# Schematic.net
KiCad netlist of a schematic drawn in Altium Designer
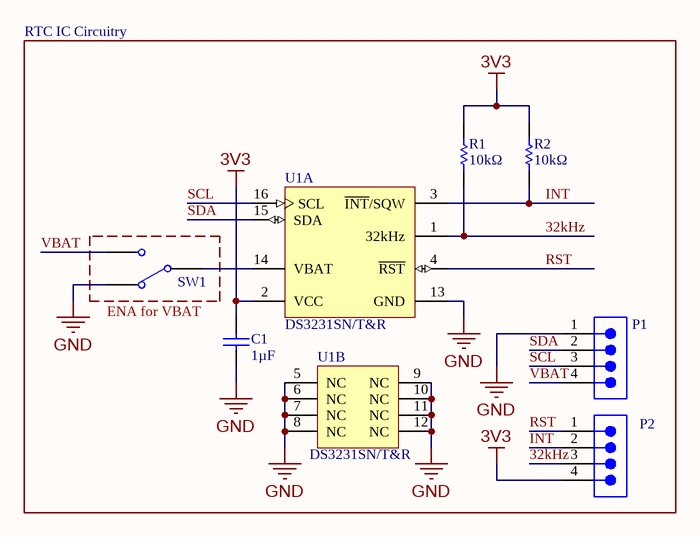
[diagram p0: Schematic.SchDoc]

(export (version "E")
  (design (tool "Eeschema 10.0.6"))
  (components
    (comp (ref "C1")
      (value "1µF")
      (footprint "CAPC3216X110X50LL20T25")
      (description "Chip Capacitor, 1 uF, +/- 10%, 50 V, -55 to 125 degC, 1206 (3216 Metric), RoHS, Tape and Reel")
      (fields (field (name "MANUFACTURER") "Kemet") (field (name "TOLERANCE") "10%"))
      (libsource (lib "Altium Content Vault") (part "CAP-NP-2"))
    )
    (comp (ref "P1")
      (value "61300411121")
      (footprint "61300411121")
      (libsource (lib "Altium Content Vault") (part "Header_Male_1R_04P"))
    )
    (comp (ref "P2")
      (value "61300411121")
      (footprint "61300411121")
      (libsource (lib "Altium Content Vault") (part "Header_Male_1R_04P"))
    )
    (comp (ref "R1")
      (value "10kΩ")
      (footprint "RESC3116X65X40LL10T20")
      (description "Chip Resistor, 10 KOhm, +/- 1%, 0.25 W, -55 to 155 degC, 1206 (3216 Metric), RoHS, Tape and Reel")
      (fields (field (name "TOLERANCE") "1%") (field (name "MANUFACTURER") "Yageo"))
      (libsource (lib "Altium Content Vault") (part "RES-2"))
    )
    (comp (ref "R2")
      (value "10kΩ")
      (footprint "RESC3116X65X40LL10T20")
      (description "Chip Resistor, 10 KOhm, +/- 1%, 0.25 W, -55 to 155 degC, 1206 (3216 Metric), RoHS, Tape and Reel")
      (fields (field (name "TOLERANCE") "1%") (field (name "MANUFACTURER") "Yageo"))
      (libsource (lib "Altium Content Vault") (part "RES-2"))
    )
    (comp (ref "SW1")
      (value "450404015514")
      (footprint "450404015514")
      (description "450404015514 Slide Switch, 0.3A, 5Vdc, Smd Rohs Compliant: Yes")
      (libsource (lib "Altium Content Vault") (part "SPDT"))
    )
    (comp (ref "U1")
      (value "DS3231SN/T&R")
      (footprint "W16-H2_N")
      (description "Extremely Accurate I2C-Integrated Real-Time Clock/TCXO/Crystal, 16-Pin SO, -40 to 85 degC, Reel")
      (libsource (lib "Altium Content Vault") (part "MAX-RTC-16-DS3231S-W16#H2"))
    )
  )
  (nets
    (net (code "1") (name "/32kHz") (class "Default")
      (node (ref "P2") (pin "3") (pinfunction "3_3") (pintype "passive"))
      (node (ref "R1") (pin "1") (pinfunction "1_1") (pintype "passive"))
      (node (ref "U1") (pin "1") (pinfunction "32kHz_1") (pintype "open_collector"))
    )
    (net (code "2") (name "/INT") (class "Default")
      (node (ref "P2") (pin "2") (pinfunction "2_2") (pintype "passive"))
      (node (ref "R2") (pin "1") (pinfunction "1_1") (pintype "passive"))
      (node (ref "U1") (pin "3") (pinfunction "~{INT}/SQW_3") (pintype "open_collector"))
    )
    (net (code "3") (name "/RST") (class "Default")
      (node (ref "P2") (pin "1") (pinfunction "1_1") (pintype "passive"))
      (node (ref "U1") (pin "4") (pinfunction "~{RST}_4") (pintype "bidirectional"))
    )
    (net (code "4") (name "/SCL") (class "Default")
      (node (ref "P1") (pin "3") (pinfunction "3_3") (pintype "passive"))
      (node (ref "U1") (pin "16") (pinfunction "SCL_16") (pintype "input"))
    )
    (net (code "5") (name "/SDA") (class "Default")
      (node (ref "P1") (pin "2") (pinfunction "2_2") (pintype "passive"))
      (node (ref "U1") (pin "15") (pinfunction "SDA_15") (pintype "bidirectional"))
    )
    (net (code "6") (name "/VBAT") (class "Default")
      (node (ref "P1") (pin "4") (pinfunction "4_4") (pintype "passive"))
      (node (ref "SW1") (pin "L2") (pinfunction "L2_L2") (pintype "passive"))
    )
    (net (code "7") (name "3V3") (class "Default")
      (node (ref "C1") (pin "2") (pinfunction "2_2") (pintype "passive"))
      (node (ref "P2") (pin "4") (pinfunction "4_4") (pintype "passive"))
      (node (ref "R1") (pin "2") (pinfunction "2_2") (pintype "passive"))
      (node (ref "R2") (pin "2") (pinfunction "2_2") (pintype "passive"))
      (node (ref "U1") (pin "2") (pinfunction "VCC_2") (pintype "power_in"))
    )
    (net (code "8") (name "GND") (class "Default")
      (node (ref "C1") (pin "1") (pinfunction "1_1") (pintype "passive"))
      (node (ref "P1") (pin "1") (pinfunction "1_1") (pintype "passive"))
      (node (ref "SW1") (pin "L1") (pinfunction "L1_L1") (pintype "passive"))
      (node (ref "U1") (pin "10") (pinfunction "NC_10") (pintype "passive"))
      (node (ref "U1") (pin "11") (pinfunction "NC_11") (pintype "passive"))
      (node (ref "U1") (pin "12") (pinfunction "NC_12") (pintype "passive"))
      (node (ref "U1") (pin "13") (pinfunction "GND_13") (pintype "power_in"))
      (node (ref "U1") (pin "5") (pinfunction "NC_5") (pintype "passive"))
      (node (ref "U1") (pin "6") (pinfunction "NC_6") (pintype "passive"))
      (node (ref "U1") (pin "7") (pinfunction "NC_7") (pintype "passive"))
      (node (ref "U1") (pin "8") (pinfunction "NC_8") (pintype "passive"))
      (node (ref "U1") (pin "9") (pinfunction "NC_9") (pintype "passive"))
    )
    (net (code "9") (name "Net-(U1A-VBAT)") (class "Default")
      (node (ref "SW1") (pin "COM") (pinfunction "COM_COM") (pintype "passive"))
      (node (ref "U1") (pin "14") (pinfunction "VBAT_14") (pintype "power_in"))
    )
  )
)
